# Shield_v1.net
KiCad netlist of a schematic drawn in EAGLE
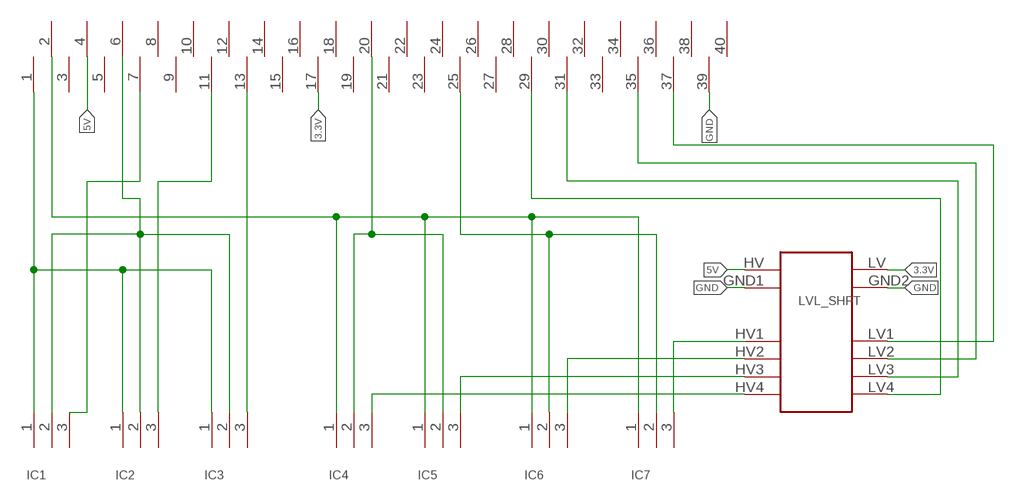
[diagram p0: schematic, sheet 1]

(export (version "E")
  (design (tool "Eeschema 10.0.6"))
  (components
    (comp (ref "IC1")
      (value "3,5MM_3PIN")
      (footprint "eagle-import:3,5MM_3PIN")
      (libsource (lib "eagle-import") (part "3,5MM_3PIN"))
    )
    (comp (ref "IC2")
      (value "3,5MM_3PIN")
      (footprint "eagle-import:3,5MM_3PIN")
      (libsource (lib "eagle-import") (part "3,5MM_3PIN"))
    )
    (comp (ref "IC3")
      (value "3,5MM_3PIN")
      (footprint "eagle-import:3,5MM_3PIN")
      (libsource (lib "eagle-import") (part "3,5MM_3PIN"))
    )
    (comp (ref "IC4")
      (value "3,5MM_3PIN")
      (footprint "eagle-import:3,5MM_3PIN")
      (libsource (lib "eagle-import") (part "3,5MM_3PIN"))
    )
    (comp (ref "IC5")
      (value "3,5MM_3PIN")
      (footprint "eagle-import:3,5MM_3PIN")
      (libsource (lib "eagle-import") (part "3,5MM_3PIN"))
    )
    (comp (ref "IC6")
      (value "3,5MM_3PIN")
      (footprint "eagle-import:3,5MM_3PIN")
      (libsource (lib "eagle-import") (part "3,5MM_3PIN"))
    )
    (comp (ref "IC7")
      (value "3,5MM_3PIN")
      (footprint "eagle-import:3,5MM_3PIN")
      (libsource (lib "eagle-import") (part "3,5MM_3PIN"))
    )
    (comp (ref "IC17")
      (value "40_PIN_2.54MM")
      (footprint "eagle-import:40_PIN_2.54MM")
      (libsource (lib "eagle-import") (part "40_PIN_2.54MM"))
    )
    (comp (ref "LVL_SHFT")
      (value "LVL_SHIFTER_4CH")
      (footprint "eagle-import:LVL_SHIFTER_4CH")
      (libsource (lib "eagle-import") (part "LVL_SHIFTER_4CH"))
    )
  )
  (nets
    (net (code "1") (name "3.3V") (class "Default")
      (node (ref "IC17") (pin "17") (pinfunction "P$17_17") (pintype "bidirectional"))
      (node (ref "LVL_SHFT") (pin "LV") (pinfunction "LV_LV") (pintype "bidirectional"))
    )
    (net (code "2") (name "5V") (class "Default")
      (node (ref "IC17") (pin "4") (pinfunction "P$4_4") (pintype "bidirectional"))
      (node (ref "LVL_SHFT") (pin "HV") (pinfunction "HV_HV") (pintype "bidirectional"))
    )
    (net (code "3") (name "GND") (class "Default")
      (node (ref "IC17") (pin "39") (pinfunction "P$39_39") (pintype "bidirectional"))
      (node (ref "LVL_SHFT") (pin "GND1") (pinfunction "GND1_GND1") (pintype "bidirectional"))
      (node (ref "LVL_SHFT") (pin "GND2") (pinfunction "GND2_GND2") (pintype "bidirectional"))
    )
    (net (code "4") (name "Net-(IC1-P$1)") (class "Default")
      (node (ref "IC1") (pin "1") (pinfunction "P$1_1") (pintype "bidirectional"))
      (node (ref "IC17") (pin "1") (pinfunction "P$1_1") (pintype "bidirectional"))
      (node (ref "IC2") (pin "1") (pinfunction "P$1_1") (pintype "bidirectional"))
      (node (ref "IC3") (pin "1") (pinfunction "P$1_1") (pintype "bidirectional"))
    )
    (net (code "5") (name "Net-(IC1-P$2)") (class "Default")
      (node (ref "IC1") (pin "2") (pinfunction "P$2_2") (pintype "bidirectional"))
      (node (ref "IC17") (pin "6") (pinfunction "P$6_6") (pintype "bidirectional"))
      (node (ref "IC2") (pin "2") (pinfunction "P$2_2") (pintype "bidirectional"))
      (node (ref "IC3") (pin "2") (pinfunction "P$2_2") (pintype "bidirectional"))
    )
    (net (code "6") (name "Net-(IC1-P$3)") (class "Default")
      (node (ref "IC1") (pin "3") (pinfunction "P$3_3") (pintype "bidirectional"))
      (node (ref "IC17") (pin "7") (pinfunction "P$7_7") (pintype "bidirectional"))
    )
    (net (code "7") (name "Net-(IC4-P$3)") (class "Default")
      (node (ref "IC4") (pin "3") (pinfunction "P$3_3") (pintype "bidirectional"))
      (node (ref "LVL_SHFT") (pin "HV4") (pinfunction "HV4_HV4") (pintype "bidirectional"))
    )
    (net (code "8") (name "Net-(IC5-P$3)") (class "Default")
      (node (ref "IC5") (pin "3") (pinfunction "P$3_3") (pintype "bidirectional"))
      (node (ref "LVL_SHFT") (pin "HV3") (pinfunction "HV3_HV3") (pintype "bidirectional"))
    )
    (net (code "9") (name "Net-(IC6-P$3)") (class "Default")
      (node (ref "IC6") (pin "3") (pinfunction "P$3_3") (pintype "bidirectional"))
      (node (ref "LVL_SHFT") (pin "HV2") (pinfunction "HV2_HV2") (pintype "bidirectional"))
    )
    (net (code "10") (name "Net-(IC7-P$3)") (class "Default")
      (node (ref "IC7") (pin "3") (pinfunction "P$3_3") (pintype "bidirectional"))
      (node (ref "LVL_SHFT") (pin "HV1") (pinfunction "HV1_HV1") (pintype "bidirectional"))
    )
    (net (code "11") (name "Net-(IC17-P$2)") (class "Default")
      (node (ref "IC17") (pin "2") (pinfunction "P$2_2") (pintype "bidirectional"))
      (node (ref "IC4") (pin "1") (pinfunction "P$1_1") (pintype "bidirectional"))
      (node (ref "IC5") (pin "1") (pinfunction "P$1_1") (pintype "bidirectional"))
      (node (ref "IC6") (pin "1") (pinfunction "P$1_1") (pintype "bidirectional"))
      (node (ref "IC7") (pin "1") (pinfunction "P$1_1") (pintype "bidirectional"))
    )
    (net (code "12") (name "Net-(IC17-P$11)") (class "Default")
      (node (ref "IC17") (pin "11") (pinfunction "P$11_11") (pintype "bidirectional"))
      (node (ref "IC2") (pin "3") (pinfunction "P$3_3") (pintype "bidirectional"))
    )
    (net (code "13") (name "Net-(IC17-P$13)") (class "Default")
      (node (ref "IC17") (pin "13") (pinfunction "P$13_13") (pintype "bidirectional"))
      (node (ref "IC3") (pin "3") (pinfunction "P$3_3") (pintype "bidirectional"))
    )
    (net (code "14") (name "Net-(IC17-P$20)") (class "Default")
      (node (ref "IC17") (pin "20") (pinfunction "P$20_20") (pintype "bidirectional"))
      (node (ref "IC4") (pin "2") (pinfunction "P$2_2") (pintype "bidirectional"))
      (node (ref "IC5") (pin "2") (pinfunction "P$2_2") (pintype "bidirectional"))
    )
    (net (code "15") (name "Net-(IC17-P$25)") (class "Default")
      (node (ref "IC17") (pin "25") (pinfunction "P$25_25") (pintype "bidirectional"))
      (node (ref "IC6") (pin "2") (pinfunction "P$2_2") (pintype "bidirectional"))
      (node (ref "IC7") (pin "2") (pinfunction "P$2_2") (pintype "bidirectional"))
    )
    (net (code "16") (name "Net-(IC17-P$29)") (class "Default")
      (node (ref "IC17") (pin "29") (pinfunction "P$29_29") (pintype "bidirectional"))
      (node (ref "LVL_SHFT") (pin "LV4") (pinfunction "LV4_LV4") (pintype "bidirectional"))
    )
    (net (code "17") (name "Net-(IC17-P$31)") (class "Default")
      (node (ref "IC17") (pin "31") (pinfunction "P$31_31") (pintype "bidirectional"))
      (node (ref "LVL_SHFT") (pin "LV3") (pinfunction "LV3_LV3") (pintype "bidirectional"))
    )
    (net (code "18") (name "Net-(IC17-P$35)") (class "Default")
      (node (ref "IC17") (pin "35") (pinfunction "P$35_35") (pintype "bidirectional"))
      (node (ref "LVL_SHFT") (pin "LV2") (pinfunction "LV2_LV2") (pintype "bidirectional"))
    )
    (net (code "19") (name "Net-(IC17-P$37)") (class "Default")
      (node (ref "IC17") (pin "37") (pinfunction "P$37_37") (pintype "bidirectional"))
      (node (ref "LVL_SHFT") (pin "LV1") (pinfunction "LV1_LV1") (pintype "bidirectional"))
    )
    (net (code "20") (name "unconnected-(IC17-P$3-Pad3)") (class "Default")
      (node (ref "IC17") (pin "3") (pinfunction "P$3_3") (pintype "bidirectional"))
    )
    (net (code "21") (name "unconnected-(IC17-P$5-Pad5)") (class "Default")
      (node (ref "IC17") (pin "5") (pinfunction "P$5_5") (pintype "bidirectional"))
    )
    (net (code "22") (name "unconnected-(IC17-P$8-Pad8)") (class "Default")
      (node (ref "IC17") (pin "8") (pinfunction "P$8_8") (pintype "bidirectional"))
    )
    (net (code "23") (name "unconnected-(IC17-P$9-Pad9)") (class "Default")
      (node (ref "IC17") (pin "9") (pinfunction "P$9_9") (pintype "bidirectional"))
    )
    (net (code "24") (name "unconnected-(IC17-P$10-Pad10)") (class "Default")
      (node (ref "IC17") (pin "10") (pinfunction "P$10_10") (pintype "bidirectional"))
    )
    (net (code "25") (name "unconnected-(IC17-P$12-Pad12)") (class "Default")
      (node (ref "IC17") (pin "12") (pinfunction "P$12_12") (pintype "bidirectional"))
    )
    (net (code "26") (name "unconnected-(IC17-P$14-Pad14)") (class "Default")
      (node (ref "IC17") (pin "14") (pinfunction "P$14_14") (pintype "bidirectional"))
    )
    (net (code "27") (name "unconnected-(IC17-P$15-Pad15)") (class "Default")
      (node (ref "IC17") (pin "15") (pinfunction "P$15_15") (pintype "bidirectional"))
    )
    (net (code "28") (name "unconnected-(IC17-P$16-Pad16)") (class "Default")
      (node (ref "IC17") (pin "16") (pinfunction "P$16_16") (pintype "bidirectional"))
    )
    (net (code "29") (name "unconnected-(IC17-P$18-Pad18)") (class "Default")
      (node (ref "IC17") (pin "18") (pinfunction "P$18_18") (pintype "bidirectional"))
    )
    (net (code "30") (name "unconnected-(IC17-P$19-Pad19)") (class "Default")
      (node (ref "IC17") (pin "19") (pinfunction "P$19_19") (pintype "bidirectional"))
    )
    (net (code "31") (name "unconnected-(IC17-P$21-Pad21)") (class "Default")
      (node (ref "IC17") (pin "21") (pinfunction "P$21_21") (pintype "bidirectional"))
    )
    (net (code "32") (name "unconnected-(IC17-P$22-Pad22)") (class "Default")
      (node (ref "IC17") (pin "22") (pinfunction "P$22_22") (pintype "bidirectional"))
    )
    (net (code "33") (name "unconnected-(IC17-P$23-Pad23)") (class "Default")
      (node (ref "IC17") (pin "23") (pinfunction "P$23_23") (pintype "bidirectional"))
    )
    (net (code "34") (name "unconnected-(IC17-P$24-Pad24)") (class "Default")
      (node (ref "IC17") (pin "24") (pinfunction "P$24_24") (pintype "bidirectional"))
    )
    (net (code "35") (name "unconnected-(IC17-P$26-Pad26)") (class "Default")
      (node (ref "IC17") (pin "26") (pinfunction "P$26_26") (pintype "bidirectional"))
    )
    (net (code "36") (name "unconnected-(IC17-P$27-Pad27)") (class "Default")
      (node (ref "IC17") (pin "27") (pinfunction "P$27_27") (pintype "bidirectional"))
    )
    (net (code "37") (name "unconnected-(IC17-P$28-Pad28)") (class "Default")
      (node (ref "IC17") (pin "28") (pinfunction "P$28_28") (pintype "bidirectional"))
    )
    (net (code "38") (name "unconnected-(IC17-P$30-Pad30)") (class "Default")
      (node (ref "IC17") (pin "30") (pinfunction "P$30_30") (pintype "bidirectional"))
    )
    (net (code "39") (name "unconnected-(IC17-P$32-Pad32)") (class "Default")
      (node (ref "IC17") (pin "32") (pinfunction "P$32_32") (pintype "bidirectional"))
    )
    (net (code "40") (name "unconnected-(IC17-P$33-Pad33)") (class "Default")
      (node (ref "IC17") (pin "33") (pinfunction "P$33_33") (pintype "bidirectional"))
    )
    (net (code "41") (name "unconnected-(IC17-P$34-Pad34)") (class "Default")
      (node (ref "IC17") (pin "34") (pinfunction "P$34_34") (pintype "bidirectional"))
    )
    (net (code "42") (name "unconnected-(IC17-P$36-Pad36)") (class "Default")
      (node (ref "IC17") (pin "36") (pinfunction "P$36_36") (pintype "bidirectional"))
    )
    (net (code "43") (name "unconnected-(IC17-P$38-Pad38)") (class "Default")
      (node (ref "IC17") (pin "38") (pinfunction "P$38_38") (pintype "bidirectional"))
    )
    (net (code "44") (name "unconnected-(IC17-P$40-Pad40)") (class "Default")
      (node (ref "IC17") (pin "40") (pinfunction "P$40_40") (pintype "bidirectional"))
    )
  )
)
